# Dazzler-noaudio.net
KiCad netlist of a schematic drawn in EAGLE
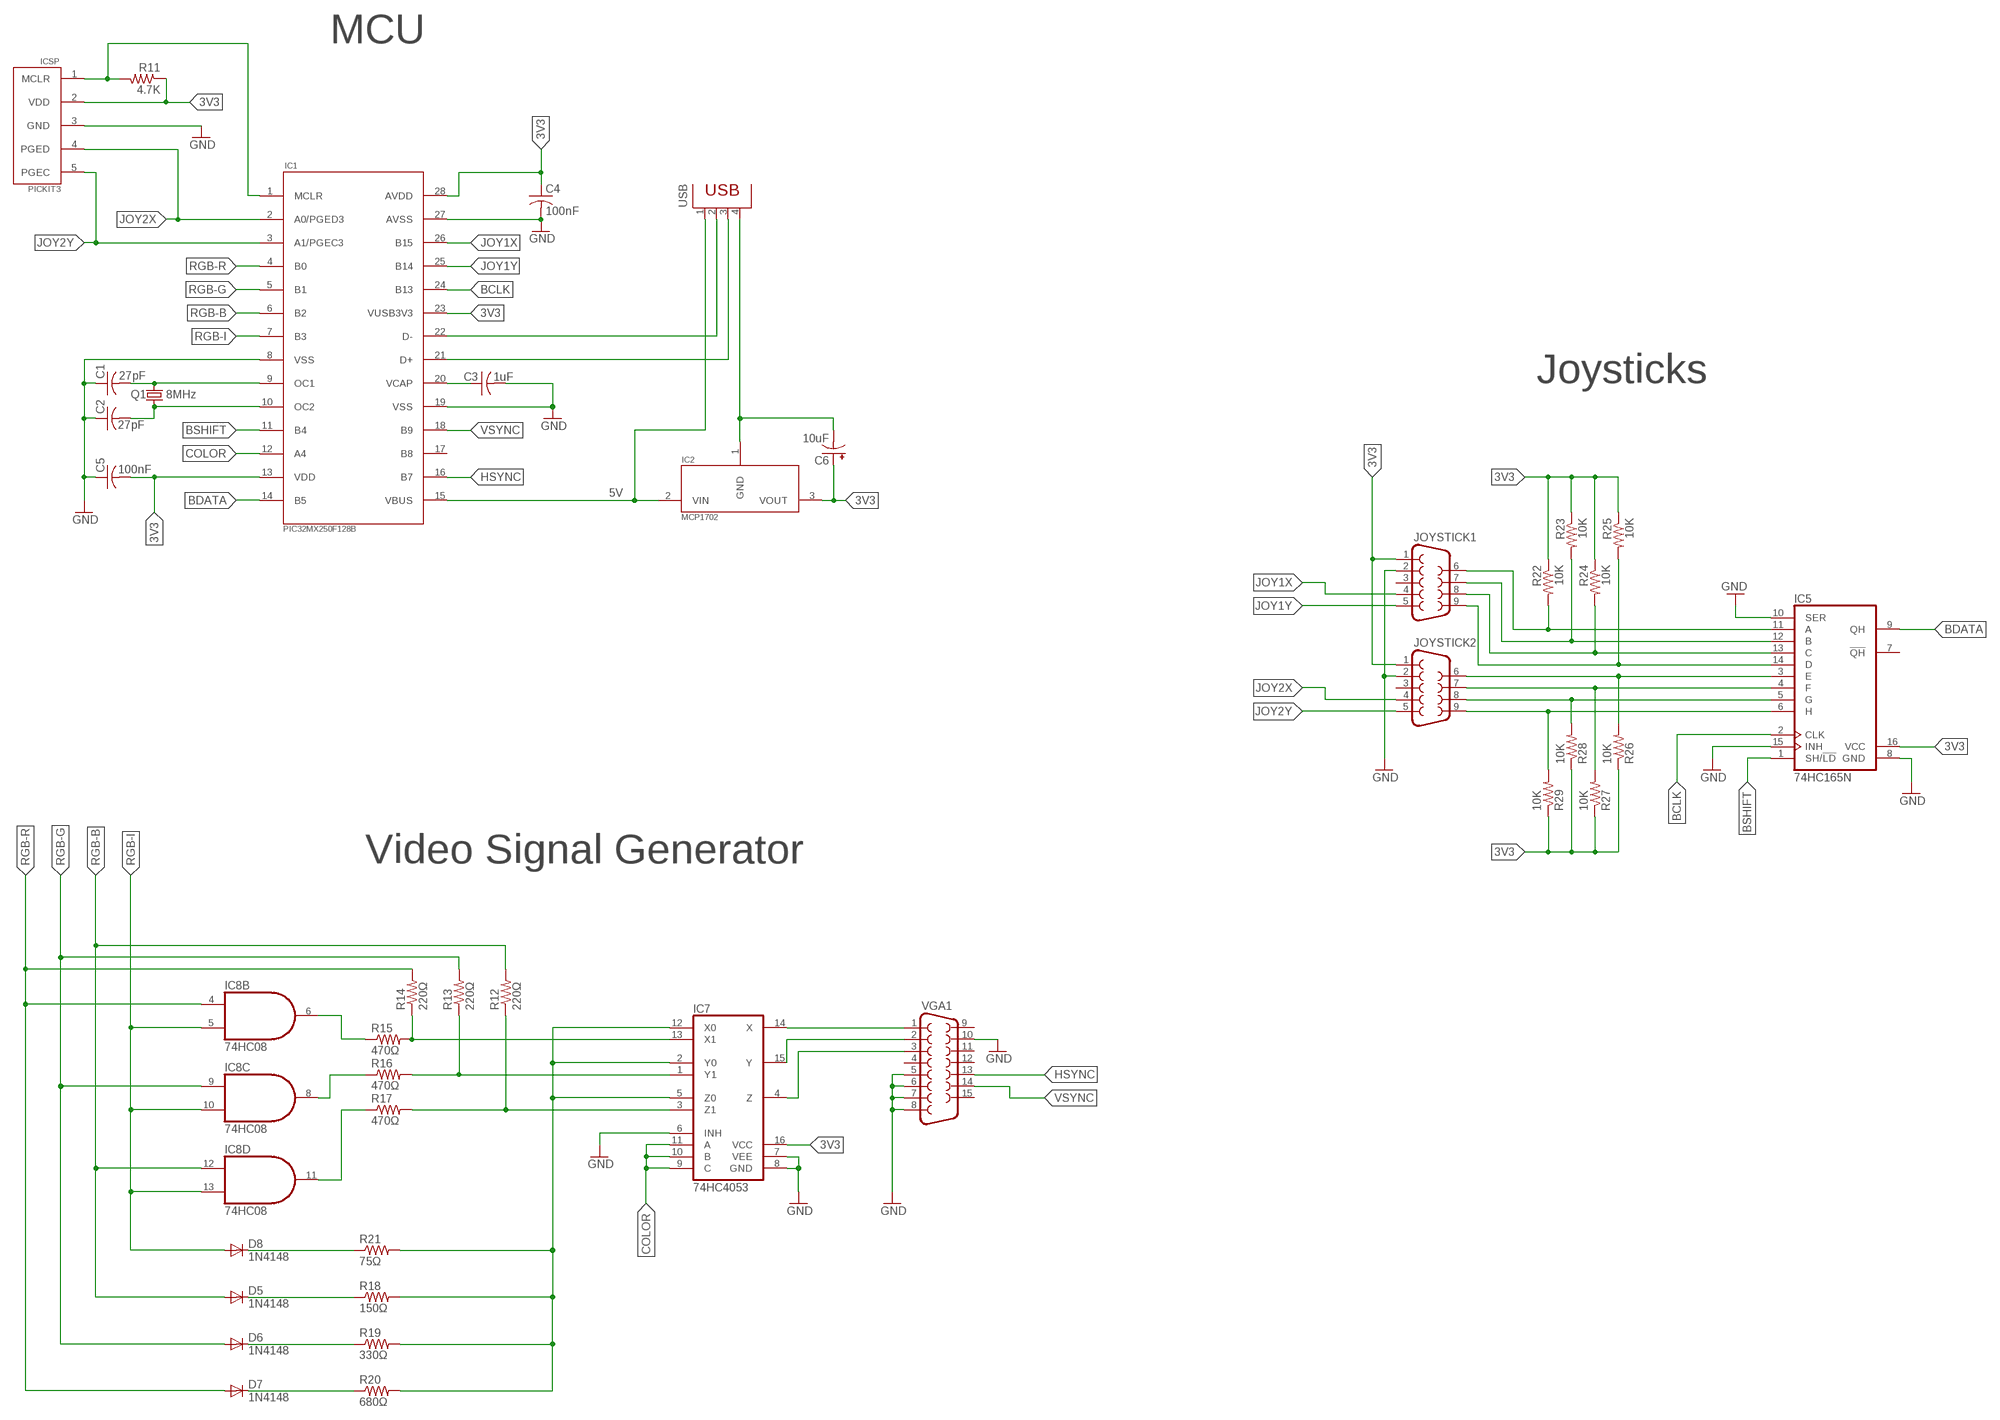
[diagram p0: schematic, sheet 1]

(export (version "E")
  (design (tool "Eeschema 10.0.6"))
  (components
    (comp (ref "C1")
      (value "27pF")
      (footprint "eagle-import:C025-024X044")
      (libsource (lib "eagle-import") (part "C-US025-024X044"))
    )
    (comp (ref "C2")
      (value "27pF")
      (footprint "eagle-import:C025-024X044")
      (libsource (lib "eagle-import") (part "C-US025-024X044"))
    )
    (comp (ref "C3")
      (value "1uF")
      (footprint "eagle-import:C025-024X044")
      (libsource (lib "eagle-import") (part "C-US025-024X044"))
    )
    (comp (ref "C4")
      (value "100nF")
      (footprint "eagle-import:C025-024X044")
      (libsource (lib "eagle-import") (part "C-US025-024X044"))
    )
    (comp (ref "C5")
      (value "100nF")
      (footprint "eagle-import:C025-024X044")
      (libsource (lib "eagle-import") (part "C-US025-024X044"))
    )
    (comp (ref "C6")
      (value "10uF")
      (footprint "eagle-import:E15-6")
      (libsource (lib "eagle-import") (part "CPOL-USE15-6AXIAL"))
    )
    (comp (ref "D5")
      (value "1N4148")
      (footprint "eagle-import:DO35-7")
      (libsource (lib "eagle-import") (part "1N4148DO35-7"))
    )
    (comp (ref "D6")
      (value "1N4148")
      (footprint "eagle-import:DO35-7")
      (libsource (lib "eagle-import") (part "1N4148DO35-7"))
    )
    (comp (ref "D7")
      (value "1N4148")
      (footprint "eagle-import:DO35-7")
      (libsource (lib "eagle-import") (part "1N4148DO35-7"))
    )
    (comp (ref "D8")
      (value "1N4148")
      (footprint "eagle-import:DO35-7")
      (libsource (lib "eagle-import") (part "1N4148DO35-7"))
    )
    (comp (ref "IC1")
      (value "PIC32MX250F128B")
      (footprint "eagle-import:DIL28-3")
      (libsource (lib "eagle-import") (part "PIC32MX250F128B"))
    )
    (comp (ref "IC2")
      (value "MCP1702")
      (footprint "eagle-import:TO92")
      (libsource (lib "eagle-import") (part "MCP1702"))
    )
    (comp (ref "IC5")
      (value "74HC165N")
      (footprint "eagle-import:DIL16")
      (libsource (lib "eagle-import") (part "74165NHC"))
    )
    (comp (ref "IC7")
      (value "74HC4053")
      (footprint "eagle-import:DIL16")
      (libsource (lib "eagle-import") (part "4053N"))
    )
    (comp (ref "IC8")
      (value "74HC08")
      (footprint "eagle-import:DIL14")
      (libsource (lib "eagle-import") (part "7408NHC"))
    )
    (comp (ref "ICSP")
      (value "PICKIT3")
      (footprint "eagle-import:1X05")
      (libsource (lib "eagle-import") (part "PICKIT3"))
    )
    (comp (ref "JOYSTICK1")
      (value "F09V")
      (footprint "eagle-import:F09V")
      (libsource (lib "eagle-import") (part "F09V"))
    )
    (comp (ref "JOYSTICK2")
      (value "F09V")
      (footprint "eagle-import:F09V")
      (libsource (lib "eagle-import") (part "F09V"))
    )
    (comp (ref "Q1")
      (value "8MHz")
      (footprint "eagle-import:HC33U-V")
      (libsource (lib "eagle-import") (part "CRYSTALHC33U-V"))
    )
    (comp (ref "R11")
      (value "4.7K")
      (footprint "eagle-import:P0613_15")
      (libsource (lib "eagle-import") (part "R-US_0613/15"))
    )
    (comp (ref "R12")
      (value "220Ω")
      (footprint "eagle-import:P0613_15")
      (libsource (lib "eagle-import") (part "R-US_0613/15"))
    )
    (comp (ref "R13")
      (value "220Ω")
      (footprint "eagle-import:P0613_15")
      (libsource (lib "eagle-import") (part "R-US_0613/15"))
    )
    (comp (ref "R14")
      (value "220Ω")
      (footprint "eagle-import:P0613_15")
      (libsource (lib "eagle-import") (part "R-US_0613/15"))
    )
    (comp (ref "R15")
      (value "470Ω")
      (footprint "eagle-import:P0613_15")
      (libsource (lib "eagle-import") (part "R-US_0613/15"))
    )
    (comp (ref "R16")
      (value "470Ω")
      (footprint "eagle-import:P0613_15")
      (libsource (lib "eagle-import") (part "R-US_0613/15"))
    )
    (comp (ref "R17")
      (value "470Ω")
      (footprint "eagle-import:P0613_15")
      (libsource (lib "eagle-import") (part "R-US_0613/15"))
    )
    (comp (ref "R18")
      (value "150Ω")
      (footprint "eagle-import:P0613_15")
      (libsource (lib "eagle-import") (part "R-US_0613/15"))
    )
    (comp (ref "R19")
      (value "330Ω")
      (footprint "eagle-import:P0613_15")
      (libsource (lib "eagle-import") (part "R-US_0613/15"))
    )
    (comp (ref "R20")
      (value "680Ω")
      (footprint "eagle-import:P0613_15")
      (libsource (lib "eagle-import") (part "R-US_0613/15"))
    )
    (comp (ref "R21")
      (value "75Ω")
      (footprint "eagle-import:P0613_15")
      (libsource (lib "eagle-import") (part "R-US_0613/15"))
    )
    (comp (ref "R22")
      (value "10K")
      (footprint "eagle-import:P0613_15")
      (libsource (lib "eagle-import") (part "R-US_0613/15"))
    )
    (comp (ref "R23")
      (value "10K")
      (footprint "eagle-import:P0613_15")
      (libsource (lib "eagle-import") (part "R-US_0613/15"))
    )
    (comp (ref "R24")
      (value "10K")
      (footprint "eagle-import:P0613_15")
      (libsource (lib "eagle-import") (part "R-US_0613/15"))
    )
    (comp (ref "R25")
      (value "10K")
      (footprint "eagle-import:P0613_15")
      (libsource (lib "eagle-import") (part "R-US_0613/15"))
    )
    (comp (ref "R26")
      (value "10K")
      (footprint "eagle-import:P0613_15")
      (libsource (lib "eagle-import") (part "R-US_0613/15"))
    )
    (comp (ref "R27")
      (value "10K")
      (footprint "eagle-import:P0613_15")
      (libsource (lib "eagle-import") (part "R-US_0613/15"))
    )
    (comp (ref "R28")
      (value "10K")
      (footprint "eagle-import:P0613_15")
      (libsource (lib "eagle-import") (part "R-US_0613/15"))
    )
    (comp (ref "R29")
      (value "10K")
      (footprint "eagle-import:P0613_15")
      (libsource (lib "eagle-import") (part "R-US_0613/15"))
    )
    (comp (ref "USB")
      (value "PN61729")
      (footprint "eagle-import:PN61729")
      (libsource (lib "eagle-import") (part "PN61729"))
    )
    (comp (ref "VGA1")
      (value "F15HDV")
      (footprint "eagle-import:HDF15V")
      (libsource (lib "eagle-import") (part "F15HDV"))
    )
  )
  (nets
    (net (code "1") (name "/5V") (class "Default")
      (node (ref "IC1") (pin "15") (pinfunction "VBUS_15") (pintype "input"))
      (node (ref "IC2") (pin "2") (pinfunction "VIN_2") (pintype "bidirectional"))
      (node (ref "USB") (pin "1") (pinfunction "1_1") (pintype "passive"))
    )
    (net (code "2") (name "3V3") (class "Default")
      (node (ref "C4") (pin "1") (pinfunction "1_1") (pintype "passive"))
      (node (ref "C5") (pin "2") (pinfunction "2_2") (pintype "passive"))
      (node (ref "C6") (pin "+") (pinfunction "+_+") (pintype "passive"))
      (node (ref "IC1") (pin "13") (pinfunction "VDD_13") (pintype "power_in"))
      (node (ref "IC1") (pin "23") (pinfunction "VUSB3V3_23") (pintype "power_in"))
      (node (ref "IC1") (pin "28") (pinfunction "AVDD_28") (pintype "power_in"))
      (node (ref "IC2") (pin "3") (pinfunction "VOUT_3") (pintype "bidirectional"))
      (node (ref "IC5") (pin "16") (pinfunction "VCC_16") (pintype "power_in"))
      (node (ref "IC7") (pin "16") (pinfunction "VCC_16") (pintype "power_in"))
      (node (ref "ICSP") (pin "2") (pinfunction "VDD_2") (pintype "power_in"))
      (node (ref "JOYSTICK1") (pin "1") (pinfunction "1_1") (pintype "passive"))
      (node (ref "JOYSTICK2") (pin "1") (pinfunction "1_1") (pintype "passive"))
      (node (ref "R11") (pin "1") (pinfunction "1_1") (pintype "passive"))
      (node (ref "R22") (pin "1") (pinfunction "1_1") (pintype "passive"))
      (node (ref "R23") (pin "1") (pinfunction "1_1") (pintype "passive"))
      (node (ref "R24") (pin "1") (pinfunction "1_1") (pintype "passive"))
      (node (ref "R25") (pin "1") (pinfunction "1_1") (pintype "passive"))
      (node (ref "R26") (pin "1") (pinfunction "1_1") (pintype "passive"))
      (node (ref "R27") (pin "1") (pinfunction "1_1") (pintype "passive"))
      (node (ref "R28") (pin "1") (pinfunction "1_1") (pintype "passive"))
      (node (ref "R29") (pin "1") (pinfunction "1_1") (pintype "passive"))
    )
    (net (code "3") (name "BCLK") (class "Default")
      (node (ref "IC1") (pin "24") (pinfunction "B13_24") (pintype "bidirectional"))
      (node (ref "IC5") (pin "2") (pinfunction "CLK_2") (pintype "input"))
    )
    (net (code "4") (name "BDATA") (class "Default")
      (node (ref "IC1") (pin "14") (pinfunction "B5_14") (pintype "bidirectional"))
      (node (ref "IC5") (pin "9") (pinfunction "QH_9") (pintype "output"))
    )
    (net (code "5") (name "BSHIFT") (class "Default")
      (node (ref "IC1") (pin "11") (pinfunction "B4_11") (pintype "bidirectional"))
      (node (ref "IC5") (pin "1") (pinfunction "SH/~{LD}_1") (pintype "input"))
    )
    (net (code "6") (name "COLOR") (class "Default")
      (node (ref "IC1") (pin "12") (pinfunction "A4_12") (pintype "bidirectional"))
      (node (ref "IC7") (pin "10") (pinfunction "B_10") (pintype "input"))
      (node (ref "IC7") (pin "11") (pinfunction "A_11") (pintype "input"))
      (node (ref "IC7") (pin "9") (pinfunction "C_9") (pintype "input"))
    )
    (net (code "7") (name "GND") (class "Default")
      (node (ref "C1") (pin "1") (pinfunction "1_1") (pintype "passive"))
      (node (ref "C2") (pin "1") (pinfunction "1_1") (pintype "passive"))
      (node (ref "C3") (pin "2") (pinfunction "2_2") (pintype "passive"))
      (node (ref "C4") (pin "2") (pinfunction "2_2") (pintype "passive"))
      (node (ref "C5") (pin "1") (pinfunction "1_1") (pintype "passive"))
      (node (ref "IC1") (pin "19") (pinfunction "VSS_19") (pintype "bidirectional"))
      (node (ref "IC1") (pin "27") (pinfunction "AVSS_27") (pintype "power_in"))
      (node (ref "IC1") (pin "8") (pinfunction "VSS_8") (pintype "power_in"))
      (node (ref "IC5") (pin "10") (pinfunction "SER_10") (pintype "input"))
      (node (ref "IC5") (pin "15") (pinfunction "INH_15") (pintype "input"))
      (node (ref "IC5") (pin "8") (pinfunction "GND_8") (pintype "power_in"))
      (node (ref "IC7") (pin "6") (pinfunction "INH_6") (pintype "input"))
      (node (ref "IC7") (pin "7") (pinfunction "VEE_7") (pintype "power_in"))
      (node (ref "IC7") (pin "8") (pinfunction "GND_8") (pintype "power_in"))
      (node (ref "ICSP") (pin "3") (pinfunction "GND_3") (pintype "power_in"))
      (node (ref "JOYSTICK1") (pin "2") (pinfunction "2_2") (pintype "passive"))
      (node (ref "JOYSTICK2") (pin "2") (pinfunction "2_2") (pintype "passive"))
      (node (ref "VGA1") (pin "10") (pinfunction "10_10") (pintype "passive"))
      (node (ref "VGA1") (pin "5") (pinfunction "5_5") (pintype "passive"))
      (node (ref "VGA1") (pin "6") (pinfunction "6_6") (pintype "passive"))
      (node (ref "VGA1") (pin "7") (pinfunction "7_7") (pintype "passive"))
      (node (ref "VGA1") (pin "8") (pinfunction "8_8") (pintype "passive"))
    )
    (net (code "8") (name "HSYNC") (class "Default")
      (node (ref "IC1") (pin "16") (pinfunction "B7_16") (pintype "bidirectional"))
      (node (ref "VGA1") (pin "13") (pinfunction "13_13") (pintype "passive"))
    )
    (net (code "9") (name "JOY1X") (class "Default")
      (node (ref "IC1") (pin "26") (pinfunction "B15_26") (pintype "bidirectional"))
      (node (ref "JOYSTICK1") (pin "4") (pinfunction "4_4") (pintype "passive"))
    )
    (net (code "10") (name "JOY1Y") (class "Default")
      (node (ref "IC1") (pin "25") (pinfunction "B14_25") (pintype "bidirectional"))
      (node (ref "JOYSTICK1") (pin "5") (pinfunction "5_5") (pintype "passive"))
    )
    (net (code "11") (name "JOY2X") (class "Default")
      (node (ref "IC1") (pin "2") (pinfunction "A0/PGED3_2") (pintype "bidirectional"))
      (node (ref "ICSP") (pin "4") (pinfunction "PGED_4") (pintype "bidirectional"))
      (node (ref "JOYSTICK2") (pin "4") (pinfunction "4_4") (pintype "passive"))
    )
    (net (code "12") (name "JOY2Y") (class "Default")
      (node (ref "IC1") (pin "3") (pinfunction "A1/PGEC3_3") (pintype "bidirectional"))
      (node (ref "ICSP") (pin "5") (pinfunction "PGEC_5") (pintype "bidirectional"))
      (node (ref "JOYSTICK2") (pin "5") (pinfunction "5_5") (pintype "passive"))
    )
    (net (code "13") (name "Net-(D5-PadC)") (class "Default")
      (node (ref "D5") (pin "C") (pinfunction "C_C") (pintype "passive"))
      (node (ref "R18") (pin "1") (pinfunction "1_1") (pintype "passive"))
    )
    (net (code "14") (name "Net-(D6-PadC)") (class "Default")
      (node (ref "D6") (pin "C") (pinfunction "C_C") (pintype "passive"))
      (node (ref "R19") (pin "1") (pinfunction "1_1") (pintype "passive"))
    )
    (net (code "15") (name "Net-(D7-PadC)") (class "Default")
      (node (ref "D7") (pin "C") (pinfunction "C_C") (pintype "passive"))
      (node (ref "R20") (pin "1") (pinfunction "1_1") (pintype "passive"))
    )
    (net (code "16") (name "Net-(D8-PadC)") (class "Default")
      (node (ref "D8") (pin "C") (pinfunction "C_C") (pintype "passive"))
      (node (ref "R21") (pin "1") (pinfunction "1_1") (pintype "passive"))
    )
    (net (code "17") (name "Net-(IC1-D+)") (class "Default")
      (node (ref "IC1") (pin "21") (pinfunction "D+_21") (pintype "bidirectional"))
      (node (ref "USB") (pin "3") (pinfunction "3_3") (pintype "passive"))
    )
    (net (code "18") (name "Net-(IC1-D-)") (class "Default")
      (node (ref "IC1") (pin "22") (pinfunction "D-_22") (pintype "bidirectional"))
      (node (ref "USB") (pin "2") (pinfunction "2_2") (pintype "passive"))
    )
    (net (code "19") (name "Net-(IC1-MCLR)") (class "Default")
      (node (ref "IC1") (pin "1") (pinfunction "MCLR_1") (pintype "bidirectional"))
      (node (ref "ICSP") (pin "1") (pinfunction "MCLR_1") (pintype "bidirectional"))
      (node (ref "R11") (pin "2") (pinfunction "2_2") (pintype "passive"))
    )
    (net (code "20") (name "Net-(IC1-OC1)") (class "Default")
      (node (ref "C1") (pin "2") (pinfunction "2_2") (pintype "passive"))
      (node (ref "IC1") (pin "9") (pinfunction "OC1_9") (pintype "bidirectional"))
      (node (ref "Q1") (pin "2") (pinfunction "2_2") (pintype "passive"))
    )
    (net (code "21") (name "Net-(IC1-OC2)") (class "Default")
      (node (ref "C2") (pin "2") (pinfunction "2_2") (pintype "passive"))
      (node (ref "IC1") (pin "10") (pinfunction "OC2_10") (pintype "bidirectional"))
      (node (ref "Q1") (pin "1") (pinfunction "1_1") (pintype "passive"))
    )
    (net (code "22") (name "Net-(IC1-VCAP)") (class "Default")
      (node (ref "C3") (pin "1") (pinfunction "1_1") (pintype "passive"))
      (node (ref "IC1") (pin "20") (pinfunction "VCAP_20") (pintype "bidirectional"))
    )
    (net (code "23") (name "Net-(IC2-GND)") (class "Default")
      (node (ref "C6") (pin "-") (pinfunction "-_-") (pintype "passive"))
      (node (ref "IC2") (pin "1") (pinfunction "GND_1") (pintype "bidirectional"))
      (node (ref "USB") (pin "4") (pinfunction "4_4") (pintype "passive"))
    )
    (net (code "24") (name "Net-(IC5-A)") (class "Default")
      (node (ref "IC5") (pin "11") (pinfunction "A_11") (pintype "input"))
      (node (ref "JOYSTICK1") (pin "6") (pinfunction "6_6") (pintype "passive"))
      (node (ref "R22") (pin "2") (pinfunction "2_2") (pintype "passive"))
    )
    (net (code "25") (name "Net-(IC5-B)") (class "Default")
      (node (ref "IC5") (pin "12") (pinfunction "B_12") (pintype "input"))
      (node (ref "JOYSTICK1") (pin "7") (pinfunction "7_7") (pintype "passive"))
      (node (ref "R23") (pin "2") (pinfunction "2_2") (pintype "passive"))
    )
    (net (code "26") (name "Net-(IC5-C)") (class "Default")
      (node (ref "IC5") (pin "13") (pinfunction "C_13") (pintype "input"))
      (node (ref "JOYSTICK1") (pin "8") (pinfunction "8_8") (pintype "passive"))
      (node (ref "R24") (pin "2") (pinfunction "2_2") (pintype "passive"))
    )
    (net (code "27") (name "Net-(IC5-D)") (class "Default")
      (node (ref "IC5") (pin "14") (pinfunction "D_14") (pintype "input"))
      (node (ref "JOYSTICK1") (pin "9") (pinfunction "9_9") (pintype "passive"))
      (node (ref "R25") (pin "2") (pinfunction "2_2") (pintype "passive"))
    )
    (net (code "28") (name "Net-(IC5-E)") (class "Default")
      (node (ref "IC5") (pin "3") (pinfunction "E_3") (pintype "input"))
      (node (ref "JOYSTICK2") (pin "6") (pinfunction "6_6") (pintype "passive"))
      (node (ref "R26") (pin "2") (pinfunction "2_2") (pintype "passive"))
    )
    (net (code "29") (name "Net-(IC5-F)") (class "Default")
      (node (ref "IC5") (pin "4") (pinfunction "F_4") (pintype "input"))
      (node (ref "JOYSTICK2") (pin "7") (pinfunction "7_7") (pintype "passive"))
      (node (ref "R27") (pin "2") (pinfunction "2_2") (pintype "passive"))
    )
    (net (code "30") (name "Net-(IC5-G)") (class "Default")
      (node (ref "IC5") (pin "5") (pinfunction "G_5") (pintype "input"))
      (node (ref "JOYSTICK2") (pin "8") (pinfunction "8_8") (pintype "passive"))
      (node (ref "R28") (pin "2") (pinfunction "2_2") (pintype "passive"))
    )
    (net (code "31") (name "Net-(IC5-H)") (class "Default")
      (node (ref "IC5") (pin "6") (pinfunction "H_6") (pintype "input"))
      (node (ref "JOYSTICK2") (pin "9") (pinfunction "9_9") (pintype "passive"))
      (node (ref "R29") (pin "2") (pinfunction "2_2") (pintype "passive"))
    )
    (net (code "32") (name "Net-(IC7-X)") (class "Default")
      (node (ref "IC7") (pin "14") (pinfunction "X_14") (pintype "bidirectional"))
      (node (ref "VGA1") (pin "1") (pinfunction "1_1") (pintype "passive"))
    )
    (net (code "33") (name "Net-(IC7-X0)") (class "Default")
      (node (ref "IC7") (pin "12") (pinfunction "X0_12") (pintype "bidirectional"))
      (node (ref "IC7") (pin "2") (pinfunction "Y0_2") (pintype "bidirectional"))
      (node (ref "IC7") (pin "5") (pinfunction "Z0_5") (pintype "bidirectional"))
      (node (ref "R18") (pin "2") (pinfunction "2_2") (pintype "passive"))
      (node (ref "R19") (pin "2") (pinfunction "2_2") (pintype "passive"))
      (node (ref "R20") (pin "2") (pinfunction "2_2") (pintype "passive"))
      (node (ref "R21") (pin "2") (pinfunction "2_2") (pintype "passive"))
    )
    (net (code "34") (name "Net-(IC7-X1)") (class "Default")
      (node (ref "IC7") (pin "13") (pinfunction "X1_13") (pintype "bidirectional"))
      (node (ref "R14") (pin "1") (pinfunction "1_1") (pintype "passive"))
      (node (ref "R15") (pin "2") (pinfunction "2_2") (pintype "passive"))
    )
    (net (code "35") (name "Net-(IC7-Y)") (class "Default")
      (node (ref "IC7") (pin "15") (pinfunction "Y_15") (pintype "bidirectional"))
      (node (ref "VGA1") (pin "2") (pinfunction "2_2") (pintype "passive"))
    )
    (net (code "36") (name "Net-(IC7-Y1)") (class "Default")
      (node (ref "IC7") (pin "1") (pinfunction "Y1_1") (pintype "bidirectional"))
      (node (ref "R13") (pin "1") (pinfunction "1_1") (pintype "passive"))
      (node (ref "R16") (pin "2") (pinfunction "2_2") (pintype "passive"))
    )
    (net (code "37") (name "Net-(IC7-Z)") (class "Default")
      (node (ref "IC7") (pin "4") (pinfunction "Z_4") (pintype "bidirectional"))
      (node (ref "VGA1") (pin "3") (pinfunction "3_3") (pintype "passive"))
    )
    (net (code "38") (name "Net-(IC7-Z1)") (class "Default")
      (node (ref "IC7") (pin "3") (pinfunction "Z1_3") (pintype "bidirectional"))
      (node (ref "R12") (pin "1") (pinfunction "1_1") (pintype "passive"))
      (node (ref "R17") (pin "2") (pinfunction "2_2") (pintype "passive"))
    )
    (net (code "39") (name "Net-(IC8B-O)") (class "Default")
      (node (ref "IC8") (pin "6") (pinfunction "O_6") (pintype "output"))
      (node (ref "R15") (pin "1") (pinfunction "1_1") (pintype "passive"))
    )
    (net (code "40") (name "Net-(IC8C-O)") (class "Default")
      (node (ref "IC8") (pin "8") (pinfunction "O_8") (pintype "output"))
      (node (ref "R16") (pin "1") (pinfunction "1_1") (pintype "passive"))
    )
    (net (code "41") (name "Net-(IC8D-O)") (class "Default")
      (node (ref "IC8") (pin "11") (pinfunction "O_11") (pintype "output"))
      (node (ref "R17") (pin "1") (pinfunction "1_1") (pintype "passive"))
    )
    (net (code "42") (name "RGB-B") (class "Default")
      (node (ref "D5") (pin "A") (pinfunction "A_A") (pintype "passive"))
      (node (ref "IC1") (pin "6") (pinfunction "B2_6") (pintype "bidirectional"))
      (node (ref "IC8") (pin "12") (pinfunction "I0_12") (pintype "input"))
      (node (ref "R12") (pin "2") (pinfunction "2_2") (pintype "passive"))
    )
    (net (code "43") (name "RGB-G") (class "Default")
      (node (ref "D6") (pin "A") (pinfunction "A_A") (pintype "passive"))
      (node (ref "IC1") (pin "5") (pinfunction "B1_5") (pintype "bidirectional"))
      (node (ref "IC8") (pin "9") (pinfunction "I0_9") (pintype "input"))
      (node (ref "R13") (pin "2") (pinfunction "2_2") (pintype "passive"))
    )
    (net (code "44") (name "RGB-I") (class "Default")
      (node (ref "D8") (pin "A") (pinfunction "A_A") (pintype "passive"))
      (node (ref "IC1") (pin "7") (pinfunction "B3_7") (pintype "bidirectional"))
      (node (ref "IC8") (pin "10") (pinfunction "I1_10") (pintype "input"))
      (node (ref "IC8") (pin "13") (pinfunction "I1_13") (pintype "input"))
      (node (ref "IC8") (pin "5") (pinfunction "I1_5") (pintype "input"))
    )
    (net (code "45") (name "RGB-R") (class "Default")
      (node (ref "D7") (pin "A") (pinfunction "A_A") (pintype "passive"))
      (node (ref "IC1") (pin "4") (pinfunction "B0_4") (pintype "bidirectional"))
      (node (ref "IC8") (pin "4") (pinfunction "I0_4") (pintype "input"))
      (node (ref "R14") (pin "2") (pinfunction "2_2") (pintype "passive"))
    )
    (net (code "46") (name "VSYNC") (class "Default")
      (node (ref "IC1") (pin "18") (pinfunction "B9_18") (pintype "bidirectional"))
      (node (ref "VGA1") (pin "14") (pinfunction "14_14") (pintype "passive"))
    )
    (net (code "47") (name "unconnected-(IC1-B8-Pad17)") (class "Default")
      (node (ref "IC1") (pin "17") (pinfunction "B8_17") (pintype "bidirectional"))
    )
    (net (code "48") (name "unconnected-(IC5-~{QH}-Pad7)") (class "Default")
      (node (ref "IC5") (pin "7") (pinfunction "~{QH}_7") (pintype "output"))
    )
    (net (code "49") (name "unconnected-(JOYSTICK1-Pad3)") (class "Default")
      (node (ref "JOYSTICK1") (pin "3") (pinfunction "3_3") (pintype "passive"))
    )
    (net (code "50") (name "unconnected-(JOYSTICK2-Pad3)") (class "Default")
      (node (ref "JOYSTICK2") (pin "3") (pinfunction "3_3") (pintype "passive"))
    )
    (net (code "51") (name "unconnected-(VGA1-Pad4)") (class "Default")
      (node (ref "VGA1") (pin "4") (pinfunction "4_4") (pintype "passive"))
    )
    (net (code "52") (name "unconnected-(VGA1-Pad9)") (class "Default")
      (node (ref "VGA1") (pin "9") (pinfunction "9_9") (pintype "passive"))
    )
    (net (code "53") (name "unconnected-(VGA1-Pad11)") (class "Default")
      (node (ref "VGA1") (pin "11") (pinfunction "11_11") (pintype "passive"))
    )
    (net (code "54") (name "unconnected-(VGA1-Pad12)") (class "Default")
      (node (ref "VGA1") (pin "12") (pinfunction "12_12") (pintype "passive"))
    )
    (net (code "55") (name "unconnected-(VGA1-Pad15)") (class "Default")
      (node (ref "VGA1") (pin "15") (pinfunction "15_15") (pintype "passive"))
    )
  )
)
